# connectors.net
KiCad netlist of a schematic drawn in EAGLE
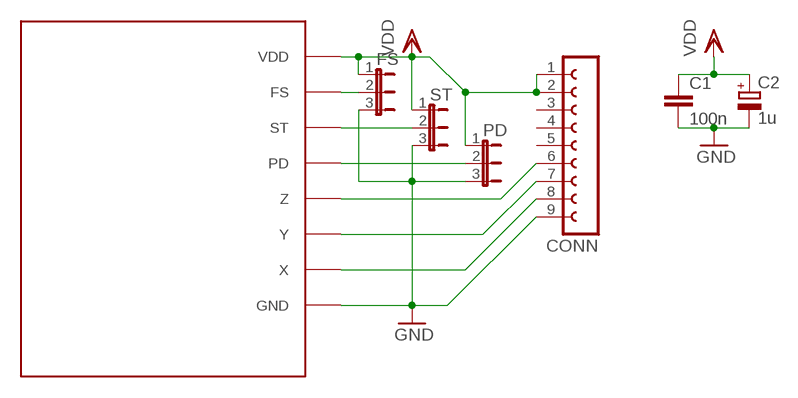
[diagram p0: schematic, sheet 1]

(export (version "E")
  (design (tool "Eeschema 10.0.6"))
  (components
    (comp (ref "C1")
      (value "100n")
      (footprint "eagle-import:C050-025X075")
      (libsource (lib "eagle-import") (part "C-EU050-025X075"))
    )
    (comp (ref "C2")
      (value "1u")
      (footprint "eagle-import:E2-5")
      (libsource (lib "eagle-import") (part "CPOL-EUE2-5"))
    )
    (comp (ref "CONN")
      (value "FE09-1")
      (footprint "eagle-import:FE09")
      (libsource (lib "eagle-import") (part "FE09-1"))
    )
    (comp (ref "FS")
      (value "JP2E")
      (footprint "eagle-import:JP2")
      (libsource (lib "eagle-import") (part "JP2E"))
    )
    (comp (ref "PD")
      (value "JP2E")
      (footprint "eagle-import:JP2")
      (libsource (lib "eagle-import") (part "JP2E"))
    )
    (comp (ref "ST")
      (value "JP2E")
      (footprint "eagle-import:JP2")
      (libsource (lib "eagle-import") (part "JP2E"))
    )
    (comp (ref "U$2")
      (value "LIS")
      (footprint "eagle-import:LIS344")
      (libsource (lib "eagle-import") (part "LIS"))
    )
  )
  (nets
    (net (code "1") (name "GND") (class "Default")
      (node (ref "C1") (pin "2") (pinfunction "2_2") (pintype "passive"))
      (node (ref "C2") (pin "-") (pinfunction "-_-") (pintype "passive"))
      (node (ref "CONN") (pin "9") (pinfunction "9_9") (pintype "passive"))
      (node (ref "FS") (pin "3") (pinfunction "3_3") (pintype "passive"))
      (node (ref "PD") (pin "3") (pinfunction "3_3") (pintype "passive"))
      (node (ref "ST") (pin "3") (pinfunction "3_3") (pintype "passive"))
      (node (ref "U$2") (pin "GND1") (pinfunction "GND_GND1") (pintype "bidirectional"))
      (node (ref "U$2") (pin "GND2") (pinfunction "GND_GND2") (pintype "bidirectional"))
      (node (ref "U$2") (pin "GND3") (pinfunction "GND_GND3") (pintype "bidirectional"))
      (node (ref "U$2") (pin "GND5") (pinfunction "GND_GND5") (pintype "bidirectional"))
    )
    (net (code "2") (name "Net-(CONN-Pad6)") (class "Default")
      (node (ref "CONN") (pin "6") (pinfunction "6_6") (pintype "passive"))
      (node (ref "U$2") (pin "Z") (pinfunction "Z_Z") (pintype "bidirectional"))
    )
    (net (code "3") (name "Net-(CONN-Pad7)") (class "Default")
      (node (ref "CONN") (pin "7") (pinfunction "7_7") (pintype "passive"))
      (node (ref "U$2") (pin "Y") (pinfunction "Y_Y") (pintype "bidirectional"))
    )
    (net (code "4") (name "Net-(CONN-Pad8)") (class "Default")
      (node (ref "CONN") (pin "8") (pinfunction "8_8") (pintype "passive"))
      (node (ref "U$2") (pin "X") (pinfunction "X_X") (pintype "bidirectional"))
    )
    (net (code "5") (name "Net-(FS-Pad2)") (class "Default")
      (node (ref "FS") (pin "2") (pinfunction "2_2") (pintype "passive"))
      (node (ref "U$2") (pin "FS") (pinfunction "FS_FS") (pintype "bidirectional"))
    )
    (net (code "6") (name "Net-(PD-Pad2)") (class "Default")
      (node (ref "PD") (pin "2") (pinfunction "2_2") (pintype "passive"))
      (node (ref "U$2") (pin "PD") (pinfunction "PD_PD") (pintype "bidirectional"))
    )
    (net (code "7") (name "Net-(ST-Pad2)") (class "Default")
      (node (ref "ST") (pin "2") (pinfunction "2_2") (pintype "passive"))
      (node (ref "U$2") (pin "ST") (pinfunction "ST_ST") (pintype "bidirectional"))
    )
    (net (code "8") (name "VDD") (class "Default")
      (node (ref "C1") (pin "1") (pinfunction "1_1") (pintype "passive"))
      (node (ref "C2") (pin "+") (pinfunction "+_+") (pintype "passive"))
      (node (ref "CONN") (pin "1") (pinfunction "1_1") (pintype "passive"))
      (node (ref "CONN") (pin "2") (pinfunction "2_2") (pintype "passive"))
      (node (ref "FS") (pin "1") (pinfunction "1_1") (pintype "passive"))
      (node (ref "PD") (pin "1") (pinfunction "1_1") (pintype "passive"))
      (node (ref "ST") (pin "1") (pinfunction "1_1") (pintype "passive"))
      (node (ref "U$2") (pin "VDD") (pinfunction "VDD_VDD") (pintype "bidirectional"))
      (node (ref "U$2") (pin "VDD2") (pinfunction "VDD_VDD2") (pintype "bidirectional"))
    )
    (net (code "9") (name "unconnected-(CONN-Pad3)") (class "Default")
      (node (ref "CONN") (pin "3") (pinfunction "3_3") (pintype "passive"))
    )
    (net (code "10") (name "unconnected-(CONN-Pad4)") (class "Default")
      (node (ref "CONN") (pin "4") (pinfunction "4_4") (pintype "passive"))
    )
    (net (code "11") (name "unconnected-(CONN-Pad5)") (class "Default")
      (node (ref "CONN") (pin "5") (pinfunction "5_5") (pintype "passive"))
    )
  )
)
